# openSX70-dongle-USB-V2.net
KiCad netlist of a schematic drawn in EAGLE
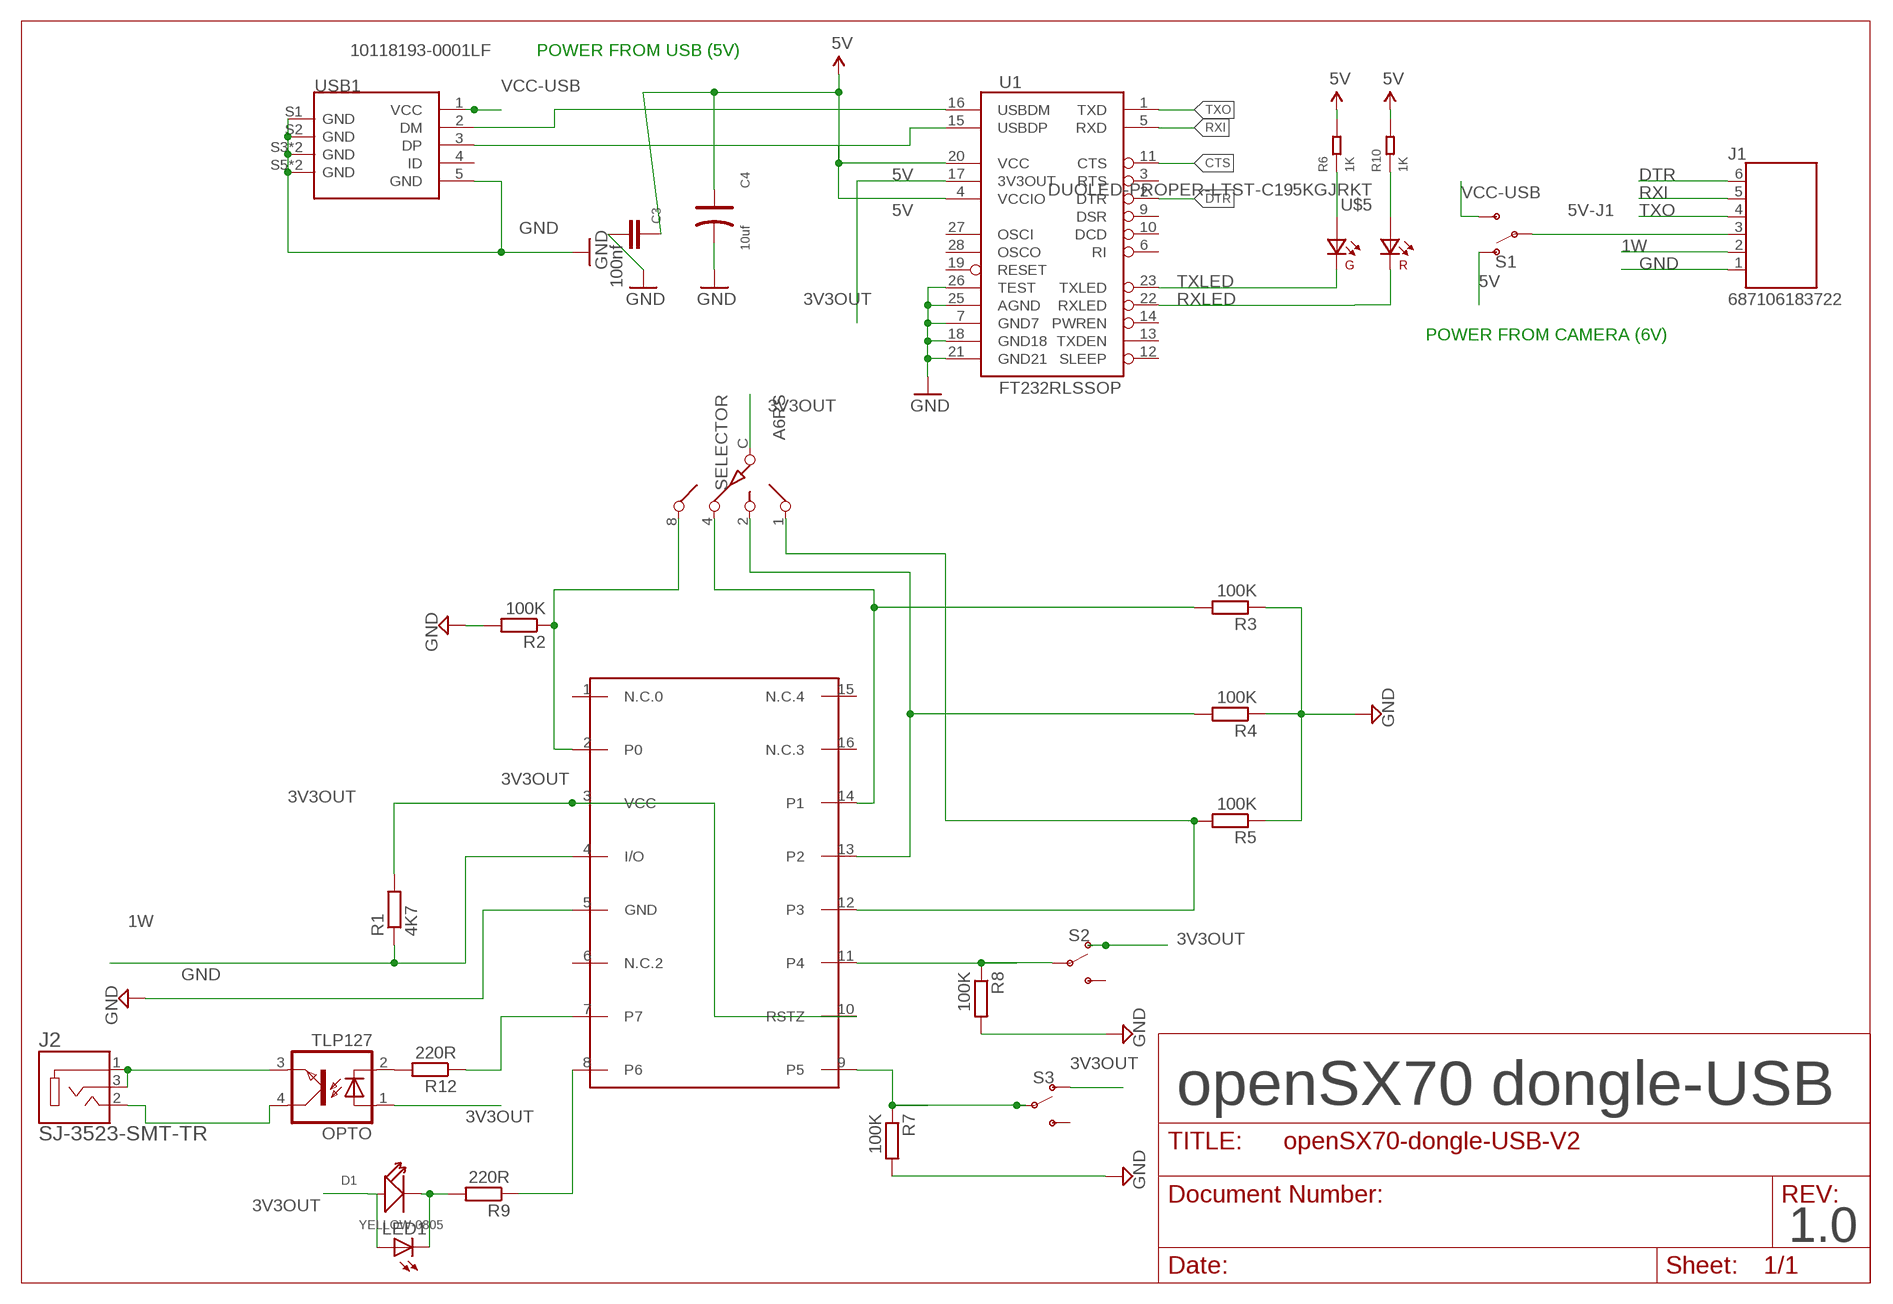
[diagram p0: schematic, sheet 1]

(export (version "E")
  (design (tool "Eeschema 10.0.6"))
  (components
    (comp (ref "C3")
      (value "100nf")
      (footprint "eagle-import:C0603")
      (libsource (lib "eagle-import") (part "C-EUC0603"))
    )
    (comp (ref "C4")
      (value "10uf")
      (footprint "eagle-import:AVX-A")
      (fields (field (name "MPN") "TAJA106K016RNJ"))
      (libsource (lib "eagle-import") (part "TANTALUM-SMD-10UF-16V-10%(AVX-A)"))
    )
    (comp (ref "D1")
      (value "YELLOW-0805")
      (footprint "eagle-import:LED-0805")
      (fields (field (name "MPN") "17-215UYC/S530-A3/TR8"))
      (libsource (lib "eagle-import") (part "SMD-LED-CLEAR-YELLOW(0805)"))
    )
    (comp (ref "DS2408")
      (value "DS2408")
      (footprint "eagle-import:SO16")
      (libsource (lib "eagle-import") (part "DS2408"))
    )
    (comp (ref "J1")
      (value "687106183722")
      (footprint "eagle-import:687106183722")
      (fields (field (name "MF") "Wurth Electronics"))
      (libsource (lib "eagle-import") (part "687106183722"))
    )
    (comp (ref "J2")
      (value "SJ-3523-SMT-TR")
      (footprint "eagle-import:CUI_SJ-3523-SMT-TR")
      (fields (field (name "MF") "CUI Inc."))
      (libsource (lib "eagle-import") (part "SJ-3523-SMT-TR"))
    )
    (comp (ref "LED1")
      (value "LED3MM")
      (footprint "eagle-import:LED3MM")
      (libsource (lib "eagle-import") (part "LED3MM"))
    )
    (comp (ref "OPTO")
      (value "TLP127")
      (footprint "eagle-import:SO-4")
      (libsource (lib "eagle-import") (part "TLP127"))
    )
    (comp (ref "R1")
      (value "4K7")
      (footprint "eagle-import:R0603")
      (libsource (lib "eagle-import") (part "R-EU_R0603"))
    )
    (comp (ref "R2")
      (value "100K")
      (footprint "eagle-import:R0603")
      (libsource (lib "eagle-import") (part "R-EU_R0603"))
    )
    (comp (ref "R3")
      (value "100K")
      (footprint "eagle-import:R0603")
      (libsource (lib "eagle-import") (part "R-EU_R0603"))
    )
    (comp (ref "R4")
      (value "100K")
      (footprint "eagle-import:R0603")
      (libsource (lib "eagle-import") (part "R-EU_R0603"))
    )
    (comp (ref "R5")
      (value "100K")
      (footprint "eagle-import:R0603")
      (libsource (lib "eagle-import") (part "R-EU_R0603"))
    )
    (comp (ref "R6")
      (value "1K")
      (footprint "eagle-import:R0603")
      (fields (field (name "MPN") "RC0603FR-071KL"))
      (libsource (lib "eagle-import") (part "SMD-RES-1K-1%-1/10W(0603)"))
    )
    (comp (ref "R7")
      (value "100K")
      (footprint "eagle-import:R0603")
      (libsource (lib "eagle-import") (part "R-EU_R0603"))
    )
    (comp (ref "R8")
      (value "100K")
      (footprint "eagle-import:R0603")
      (libsource (lib "eagle-import") (part "R-EU_R0603"))
    )
    (comp (ref "R9")
      (value "220R")
      (footprint "eagle-import:R0603")
      (libsource (lib "eagle-import") (part "R-EU_R0603"))
    )
    (comp (ref "R10")
      (value "1K")
      (footprint "eagle-import:R0603")
      (fields (field (name "MPN") "RC0603FR-071KL"))
      (libsource (lib "eagle-import") (part "SMD-RES-1K-1%-1/10W(0603)"))
    )
    (comp (ref "R12")
      (value "220R")
      (footprint "eagle-import:R0603")
      (libsource (lib "eagle-import") (part "R-EU_R0603"))
    )
    (comp (ref "S1")
      (value "SWITCH-SPDT-SMD-RIGHT-ANGLE")
      (footprint "eagle-import:SWITCH_SPST_SMD_A")
      (libsource (lib "eagle-import") (part "SWITCH-SPDT-SMD-RIGHT-ANGLE"))
    )
    (comp (ref "S2")
      (value "SWITCH-SPDT-SMD-RIGHT-ANGLE")
      (footprint "eagle-import:SWITCH_SPST_SMD_A")
      (libsource (lib "eagle-import") (part "SWITCH-SPDT-SMD-RIGHT-ANGLE"))
    )
    (comp (ref "S3")
      (value "SWITCH-SPDT-SMD-RIGHT-ANGLE")
      (footprint "eagle-import:SWITCH_SPST_SMD_A")
      (libsource (lib "eagle-import") (part "SWITCH-SPDT-SMD-RIGHT-ANGLE"))
    )
    (comp (ref "SELECTOR")
      (value "A6RS")
      (footprint "eagle-import:A6RS-161RS")
      (libsource (lib "eagle-import") (part "A6RS"))
    )
    (comp (ref "U$5")
      (value "DUOLED-PROPER-LTST-C195KGJRKT")
      (footprint "eagle-import:LTST-BILED-15X16")
      (fields (field (name "MF") "Lite-On Inc.") (field (name "MP") "LTST-C195KGJRKT"))
      (libsource (lib "eagle-import") (part "DUOLED-PROPER-LTST-C195KGJRKT"))
    )
    (comp (ref "U1")
      (value "FT232RLSSOP")
      (footprint "eagle-import:SSOP28DB")
      (libsource (lib "eagle-import") (part "FT232RLSSOP"))
    )
    (comp (ref "USB1")
      (value "10118193-0001LF")
      (footprint "eagle-import:MICRO-USB5+6P-SMD-0.65-B")
      (libsource (lib "eagle-import") (part "MICRO-USB-SMD-B-(10118193-0001LF)"))
    )
  )
  (nets
    (net (code "1") (name "/1W") (class "Default")
      (node (ref "DS2408") (pin "4") (pinfunction "I/O_4") (pintype "bidirectional"))
      (node (ref "J1") (pin "2") (pinfunction "5_2") (pintype "passive"))
      (node (ref "R1") (pin "1") (pinfunction "1_1") (pintype "passive"))
    )
    (net (code "2") (name "/3V3OUT") (class "Default")
      (node (ref "D1") (pin "+") (pinfunction "+_+") (pintype "passive"))
      (node (ref "DS2408") (pin "10") (pinfunction "RSTZ_10") (pintype "bidirectional"))
      (node (ref "DS2408") (pin "3") (pinfunction "VCC_3") (pintype "bidirectional"))
      (node (ref "LED1") (pin "A") (pinfunction "A_A") (pintype "passive"))
      (node (ref "OPTO") (pin "1") (pinfunction "A_1") (pintype "passive"))
      (node (ref "R1") (pin "2") (pinfunction "2_2") (pintype "passive"))
      (node (ref "S2") (pin "1") (pinfunction "O_1") (pintype "passive"))
      (node (ref "S3") (pin "1") (pinfunction "O_1") (pintype "passive"))
      (node (ref "SELECTOR") (pin "C") (pinfunction "C_C") (pintype "passive"))
      (node (ref "U1") (pin "17") (pinfunction "3V3OUT_17") (pintype "output"))
    )
    (net (code "3") (name "/5V-J1") (class "Default")
      (node (ref "J1") (pin "3") (pinfunction "4_3") (pintype "passive"))
      (node (ref "S1") (pin "2") (pinfunction "P_2") (pintype "passive"))
    )
    (net (code "4") (name "/RXLED") (class "Default")
      (node (ref "U$5") (pin "P$4") (pinfunction "K2_P$4") (pintype "passive"))
      (node (ref "U1") (pin "22") (pinfunction "RXLED_22") (pintype "input"))
    )
    (net (code "5") (name "/TXLED") (class "Default")
      (node (ref "U$5") (pin "P$3") (pinfunction "K1_P$3") (pintype "passive"))
      (node (ref "U1") (pin "23") (pinfunction "TXLED_23") (pintype "input"))
    )
    (net (code "6") (name "/VCC-USB") (class "Default")
      (node (ref "S1") (pin "3") (pinfunction "S_3") (pintype "passive"))
      (node (ref "USB1") (pin "1") (pinfunction "VCC_1") (pintype "bidirectional"))
    )
    (net (code "7") (name "5V") (class "Default")
      (node (ref "C3") (pin "1") (pinfunction "1_1") (pintype "passive"))
      (node (ref "C4") (pin "+") (pinfunction "+_+") (pintype "passive"))
      (node (ref "R10") (pin "2") (pinfunction "2_2") (pintype "passive"))
      (node (ref "R6") (pin "2") (pinfunction "2_2") (pintype "passive"))
      (node (ref "S1") (pin "1") (pinfunction "O_1") (pintype "passive"))
      (node (ref "U1") (pin "20") (pinfunction "VCC_20") (pintype "power_in"))
      (node (ref "U1") (pin "4") (pinfunction "VCCIO_4") (pintype "power_in"))
    )
    (net (code "8") (name "CTS") (class "Default")
      (node (ref "U1") (pin "11") (pinfunction "CTS_11") (pintype "input"))
    )
    (net (code "9") (name "DTR") (class "Default")
      (node (ref "J1") (pin "6") (pinfunction "1_6") (pintype "passive"))
      (node (ref "U1") (pin "2") (pinfunction "DTR_2") (pintype "output"))
    )
    (net (code "10") (name "GND") (class "Default")
      (node (ref "C3") (pin "2") (pinfunction "2_2") (pintype "passive"))
      (node (ref "C4") (pin "-") (pinfunction "-_-") (pintype "passive"))
      (node (ref "DS2408") (pin "5") (pinfunction "GND_5") (pintype "bidirectional"))
      (node (ref "J1") (pin "1") (pinfunction "6_1") (pintype "passive"))
      (node (ref "R2") (pin "2") (pinfunction "2_2") (pintype "passive"))
      (node (ref "R3") (pin "1") (pinfunction "1_1") (pintype "passive"))
      (node (ref "R4") (pin "1") (pinfunction "1_1") (pintype "passive"))
      (node (ref "R5") (pin "1") (pinfunction "1_1") (pintype "passive"))
      (node (ref "R7") (pin "2") (pinfunction "2_2") (pintype "passive"))
      (node (ref "R8") (pin "2") (pinfunction "2_2") (pintype "passive"))
      (node (ref "U1") (pin "18") (pinfunction "GND18_18") (pintype "power_in"))
      (node (ref "U1") (pin "21") (pinfunction "GND21_21") (pintype "power_in"))
      (node (ref "U1") (pin "25") (pinfunction "AGND_25") (pintype "power_in"))
      (node (ref "U1") (pin "26") (pinfunction "TEST_26") (pintype "input"))
      (node (ref "U1") (pin "7") (pinfunction "GND7_7") (pintype "power_in"))
      (node (ref "USB1") (pin "5") (pinfunction "GND_5") (pintype "bidirectional"))
      (node (ref "USB1") (pin "S1") (pinfunction "GND_S1") (pintype "bidirectional"))
      (node (ref "USB1") (pin "S2") (pinfunction "GND_S2") (pintype "bidirectional"))
      (node (ref "USB1") (pin "S3") (pinfunction "GND_S3") (pintype "bidirectional"))
      (node (ref "USB1") (pin "S4") (pinfunction "GND_S4") (pintype "bidirectional"))
      (node (ref "USB1") (pin "S5") (pinfunction "GND_S5") (pintype "bidirectional"))
      (node (ref "USB1") (pin "S6") (pinfunction "GND_S6") (pintype "bidirectional"))
    )
    (net (code "11") (name "Net-(DS2408-P0)") (class "Default")
      (node (ref "DS2408") (pin "2") (pinfunction "P0_2") (pintype "bidirectional"))
      (node (ref "R2") (pin "1") (pinfunction "1_1") (pintype "passive"))
      (node (ref "SELECTOR") (pin "8") (pinfunction "8_8") (pintype "passive"))
    )
    (net (code "12") (name "Net-(DS2408-P1)") (class "Default")
      (node (ref "DS2408") (pin "14") (pinfunction "P1_14") (pintype "bidirectional"))
      (node (ref "R3") (pin "2") (pinfunction "2_2") (pintype "passive"))
      (node (ref "SELECTOR") (pin "4") (pinfunction "4_4") (pintype "passive"))
    )
    (net (code "13") (name "Net-(DS2408-P2)") (class "Default")
      (node (ref "DS2408") (pin "13") (pinfunction "P2_13") (pintype "bidirectional"))
      (node (ref "R4") (pin "2") (pinfunction "2_2") (pintype "passive"))
      (node (ref "SELECTOR") (pin "2") (pinfunction "2_2") (pintype "passive"))
    )
    (net (code "14") (name "Net-(DS2408-P3)") (class "Default")
      (node (ref "DS2408") (pin "12") (pinfunction "P3_12") (pintype "bidirectional"))
      (node (ref "R5") (pin "2") (pinfunction "2_2") (pintype "passive"))
      (node (ref "SELECTOR") (pin "1") (pinfunction "1_1") (pintype "passive"))
    )
    (net (code "15") (name "Net-(DS2408-P4)") (class "Default")
      (node (ref "DS2408") (pin "11") (pinfunction "P4_11") (pintype "bidirectional"))
      (node (ref "R8") (pin "1") (pinfunction "1_1") (pintype "passive"))
      (node (ref "S2") (pin "2") (pinfunction "P_2") (pintype "passive"))
    )
    (net (code "16") (name "Net-(DS2408-P5)") (class "Default")
      (node (ref "DS2408") (pin "9") (pinfunction "P5_9") (pintype "bidirectional"))
      (node (ref "R7") (pin "1") (pinfunction "1_1") (pintype "passive"))
      (node (ref "S3") (pin "2") (pinfunction "P_2") (pintype "passive"))
    )
    (net (code "17") (name "Net-(DS2408-P6)") (class "Default")
      (node (ref "DS2408") (pin "8") (pinfunction "P6_8") (pintype "bidirectional"))
      (node (ref "R9") (pin "1") (pinfunction "1_1") (pintype "passive"))
    )
    (net (code "18") (name "Net-(DS2408-P7)") (class "Default")
      (node (ref "DS2408") (pin "7") (pinfunction "P7_7") (pintype "bidirectional"))
      (node (ref "R12") (pin "1") (pinfunction "1_1") (pintype "passive"))
    )
    (net (code "19") (name "Net-(LED1-C)") (class "Default")
      (node (ref "D1") (pin "-") (pinfunction "-_-") (pintype "passive"))
      (node (ref "LED1") (pin "K") (pinfunction "C_K") (pintype "passive"))
      (node (ref "R9") (pin "2") (pinfunction "2_2") (pintype "passive"))
    )
    (net (code "20") (name "Net-(OPTO-C)") (class "Default")
      (node (ref "OPTO") (pin "2") (pinfunction "C_2") (pintype "passive"))
      (node (ref "R12") (pin "2") (pinfunction "2_2") (pintype "passive"))
    )
    (net (code "21") (name "Net-(OPTO-COL)") (class "Default")
      (node (ref "J2") (pin "2") (pinfunction "2_2") (pintype "passive"))
      (node (ref "OPTO") (pin "4") (pinfunction "COL_4") (pintype "passive"))
    )
    (net (code "22") (name "Net-(OPTO-EMIT)") (class "Default")
      (node (ref "J2") (pin "1") (pinfunction "1_1") (pintype "passive"))
      (node (ref "J2") (pin "3") (pinfunction "3_3") (pintype "passive"))
      (node (ref "OPTO") (pin "3") (pinfunction "EMIT_3") (pintype "passive"))
    )
    (net (code "23") (name "Net-(U$5-A1)") (class "Default")
      (node (ref "R6") (pin "1") (pinfunction "1_1") (pintype "passive"))
      (node (ref "U$5") (pin "P$1") (pinfunction "A1_P$1") (pintype "passive"))
    )
    (net (code "24") (name "Net-(U$5-A2)") (class "Default")
      (node (ref "R10") (pin "1") (pinfunction "1_1") (pintype "passive"))
      (node (ref "U$5") (pin "P$2") (pinfunction "A2_P$2") (pintype "passive"))
    )
    (net (code "25") (name "Net-(U1-USBDM)") (class "Default")
      (node (ref "U1") (pin "16") (pinfunction "USBDM_16") (pintype "bidirectional"))
      (node (ref "USB1") (pin "2") (pinfunction "DM_2") (pintype "bidirectional"))
    )
    (net (code "26") (name "Net-(U1-USBDP)") (class "Default")
      (node (ref "U1") (pin "15") (pinfunction "USBDP_15") (pintype "bidirectional"))
      (node (ref "USB1") (pin "3") (pinfunction "DP_3") (pintype "bidirectional"))
    )
    (net (code "27") (name "RXI") (class "Default")
      (node (ref "J1") (pin "5") (pinfunction "2_5") (pintype "passive"))
      (node (ref "U1") (pin "5") (pinfunction "RXD_5") (pintype "input"))
    )
    (net (code "28") (name "TXO") (class "Default")
      (node (ref "J1") (pin "4") (pinfunction "3_4") (pintype "passive"))
      (node (ref "U1") (pin "1") (pinfunction "TXD_1") (pintype "output"))
    )
    (net (code "29") (name "unconnected-(DS2408-N.C.0-Pad1)") (class "Default")
      (node (ref "DS2408") (pin "1") (pinfunction "N.C.0_1") (pintype "bidirectional"))
    )
    (net (code "30") (name "unconnected-(DS2408-N.C.2-Pad6)") (class "Default")
      (node (ref "DS2408") (pin "6") (pinfunction "N.C.2_6") (pintype "bidirectional"))
    )
    (net (code "31") (name "unconnected-(DS2408-N.C.3-Pad16)") (class "Default")
      (node (ref "DS2408") (pin "16") (pinfunction "N.C.3_16") (pintype "bidirectional"))
    )
    (net (code "32") (name "unconnected-(DS2408-N.C.4-Pad15)") (class "Default")
      (node (ref "DS2408") (pin "15") (pinfunction "N.C.4_15") (pintype "bidirectional"))
    )
    (net (code "33") (name "unconnected-(S2-S-Pad3)") (class "Default")
      (node (ref "S2") (pin "3") (pinfunction "S_3") (pintype "passive"))
    )
    (net (code "34") (name "unconnected-(S3-S-Pad3)") (class "Default")
      (node (ref "S3") (pin "3") (pinfunction "S_3") (pintype "passive"))
    )
    (net (code "35") (name "unconnected-(U1-DCD-Pad10)") (class "Default")
      (node (ref "U1") (pin "10") (pinfunction "DCD_10") (pintype "input"))
    )
    (net (code "36") (name "unconnected-(U1-DSR-Pad9)") (class "Default")
      (node (ref "U1") (pin "9") (pinfunction "DSR_9") (pintype "input"))
    )
    (net (code "37") (name "unconnected-(U1-OSCI-Pad27)") (class "Default")
      (node (ref "U1") (pin "27") (pinfunction "OSCI_27") (pintype "input"))
    )
    (net (code "38") (name "unconnected-(U1-OSCO-Pad28)") (class "Default")
      (node (ref "U1") (pin "28") (pinfunction "OSCO_28") (pintype "output"))
    )
    (net (code "39") (name "unconnected-(U1-PWREN-Pad14)") (class "Default")
      (node (ref "U1") (pin "14") (pinfunction "PWREN_14") (pintype "input"))
    )
    (net (code "40") (name "unconnected-(U1-RESET-Pad19)") (class "Default")
      (node (ref "U1") (pin "19") (pinfunction "RESET_19") (pintype "input"))
    )
    (net (code "41") (name "unconnected-(U1-RI-Pad6)") (class "Default")
      (node (ref "U1") (pin "6") (pinfunction "RI_6") (pintype "input"))
    )
    (net (code "42") (name "unconnected-(U1-RTS-Pad3)") (class "Default")
      (node (ref "U1") (pin "3") (pinfunction "RTS_3") (pintype "output"))
    )
    (net (code "43") (name "unconnected-(U1-SLEEP-Pad12)") (class "Default")
      (node (ref "U1") (pin "12") (pinfunction "SLEEP_12") (pintype "input"))
    )
    (net (code "44") (name "unconnected-(U1-TXDEN-Pad13)") (class "Default")
      (node (ref "U1") (pin "13") (pinfunction "TXDEN_13") (pintype "input"))
    )
    (net (code "45") (name "unconnected-(USB1-ID-Pad4)") (class "Default")
      (node (ref "USB1") (pin "4") (pinfunction "ID_4") (pintype "bidirectional"))
    )
  )
)
